# EMS_esp32_wifi_v2_5.net
KiCad netlist of a schematic drawn in EAGLE
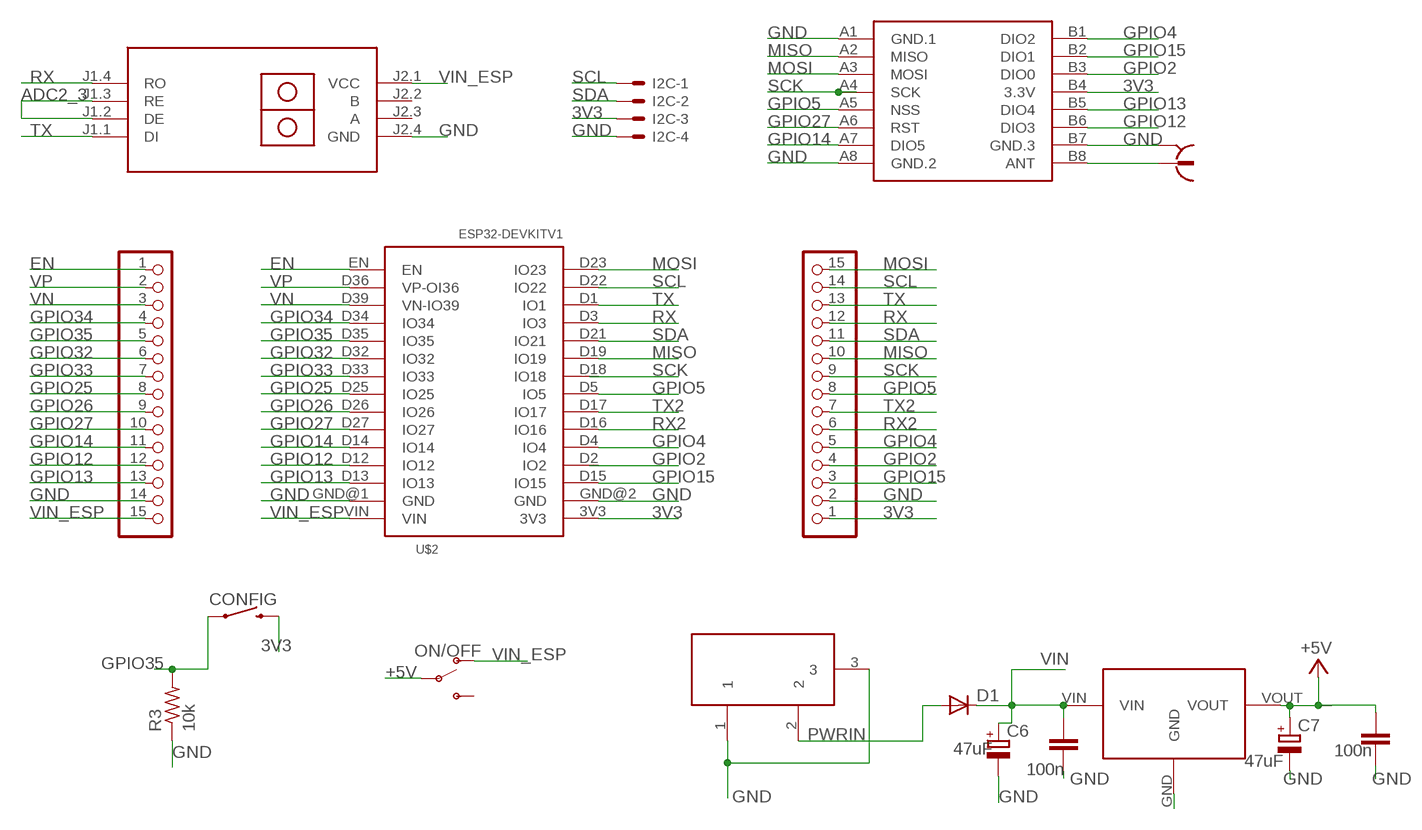
[diagram p0: schematic, sheet 1]

(export (version "E")
  (design (tool "Eeschema 10.0.6"))
  (components
    (comp (ref "C5")
      (value "100n")
      (footprint "eagle-import:C1206")
      (libsource (lib "eagle-import") (part "C-EUC1206"))
    )
    (comp (ref "C6")
      (value "47uF")
      (footprint "eagle-import:PANASONIC_D")
      (libsource (lib "eagle-import") (part "CPOL-EUD"))
    )
    (comp (ref "C7")
      (value "47uF")
      (footprint "eagle-import:PANASONIC_D")
      (libsource (lib "eagle-import") (part "CPOL-EUD"))
    )
    (comp (ref "C14")
      (value "100n")
      (footprint "eagle-import:C1206")
      (libsource (lib "eagle-import") (part "C-EUC1206"))
    )
    (comp (ref "CONFIG")
      (value "MOMENTARY-SWITCH-SPST-PTH-6.0MM")
      (footprint "eagle-import:TACTILE_SWITCH_PTH_6.0MM")
      (libsource (lib "eagle-import") (part "MOMENTARY-SWITCH-SPST-PTH-6.0MM"))
    )
    (comp (ref "D1")
      (value "DIODE-SMB")
      (footprint "eagle-import:SMB")
      (libsource (lib "eagle-import") (part "DIODE-SMB"))
    )
    (comp (ref "I2C")
      (value "22-23-2041")
      (footprint "eagle-import:22-23-2041")
      (fields (field (name "MF") "MOLEX"))
      (libsource (lib "eagle-import") (part "22-23-2041"))
    )
    (comp (ref "JP1")
      (value "PINHD-1X15")
      (footprint "eagle-import:1X15")
      (libsource (lib "eagle-import") (part "PINHD-1X15"))
    )
    (comp (ref "JP2")
      (value "PINHD-1X15")
      (footprint "eagle-import:1X15")
      (libsource (lib "eagle-import") (part "PINHD-1X15"))
    )
    (comp (ref "ON/OFF")
      (value "SWITCH-SPDT-PTH-11.6X4.0MM")
      (footprint "eagle-import:SWITCH_SPDT_PTH_11.6X4.0MM")
      (libsource (lib "eagle-import") (part "SWITCH-SPDT-PTH-11.6X4.0MM"))
    )
    (comp (ref "R3")
      (value "10k")
      (footprint "eagle-import:0204_7")
      (libsource (lib "eagle-import") (part "R-US_0204/7"))
    )
    (comp (ref "U$1")
      (value "RS485-TTL-CONVERTER")
      (footprint "eagle-import:RS485-TTL-CONVERTER")
      (libsource (lib "eagle-import") (part "RS485-TTL-CONVERTER"))
    )
    (comp (ref "U$2")
      (value "ESP32DEVKITV1")
      (footprint "eagle-import:ESP32-DEVKITV1")
      (libsource (lib "eagle-import") (part "ESP32DEVKITV1"))
    )
    (comp (ref "U$3")
      (value "SMARTPRJ_POWERSUPPLY_DC21MMX")
      (footprint "eagle-import:SMARTPRJ_POWERSUPPLY_DC-21MM")
      (libsource (lib "eagle-import") (part "SMARTPRJ_POWERSUPPLY_DC21MMX"))
    )
    (comp (ref "U$4")
      (value "7805-TO263_7805")
      (footprint "eagle-import:7805-TO263_TO263")
      (libsource (lib "eagle-import") (part "7805-TO263_7805"))
    )
    (comp (ref "U$5")
      (value "WIRELESS-LORA-RFM95W#SMD")
      (footprint "eagle-import:WIRELESS-LORA-RFM95W#SMD")
      (libsource (lib "eagle-import") (part "WIRELESS-LORA-RFM95W#SMD"))
    )
    (comp (ref "X1")
      (value "734120110")
      (footprint "eagle-import:734120110")
      (libsource (lib "eagle-import") (part "734120110"))
    )
  )
  (nets
    (net (code "1") (name "+5V") (class "Default")
      (node (ref "C14") (pin "2") (pinfunction "2_2") (pintype "passive"))
      (node (ref "C7") (pin "+") (pinfunction "+_+") (pintype "passive"))
      (node (ref "ON/OFF") (pin "2") (pinfunction "P_2") (pintype "passive"))
      (node (ref "U$4") (pin "VOUT") (pinfunction "VOUT_VOUT") (pintype "bidirectional"))
    )
    (net (code "2") (name "/3V3") (class "Default")
      (node (ref "CONFIG") (pin "3") (pinfunction "2_3") (pintype "passive"))
      (node (ref "I2C") (pin "3") (pinfunction "S_3") (pintype "passive"))
      (node (ref "JP2") (pin "1") (pinfunction "1_1") (pintype "passive"))
      (node (ref "U$2") (pin "3V3") (pinfunction "3V3_3V3") (pintype "bidirectional"))
      (node (ref "U$5") (pin "B4") (pinfunction "3.3V_B4") (pintype "power_in"))
    )
    (net (code "3") (name "/ADC2_3") (class "Default")
      (node (ref "U$1") (pin "J1.2") (pinfunction "DE_J1.2") (pintype "passive"))
      (node (ref "U$1") (pin "J1.3") (pinfunction "RE_J1.3") (pintype "passive"))
    )
    (net (code "4") (name "/EN") (class "Default")
      (node (ref "JP1") (pin "1") (pinfunction "1_1") (pintype "passive"))
      (node (ref "U$2") (pin "EN") (pinfunction "EN_EN") (pintype "bidirectional"))
    )
    (net (code "5") (name "/GND") (class "Default")
      (node (ref "C14") (pin "1") (pinfunction "1_1") (pintype "passive"))
      (node (ref "C5") (pin "1") (pinfunction "1_1") (pintype "passive"))
      (node (ref "C6") (pin "-") (pinfunction "-_-") (pintype "passive"))
      (node (ref "C7") (pin "-") (pinfunction "-_-") (pintype "passive"))
      (node (ref "I2C") (pin "4") (pinfunction "S_4") (pintype "passive"))
      (node (ref "JP1") (pin "14") (pinfunction "14_14") (pintype "passive"))
      (node (ref "JP2") (pin "2") (pinfunction "2_2") (pintype "passive"))
      (node (ref "R3") (pin "1") (pinfunction "1_1") (pintype "passive"))
      (node (ref "U$1") (pin "J2.4") (pinfunction "GND_J2.4") (pintype "power_in"))
      (node (ref "U$2") (pin "GND@1") (pinfunction "GND_GND@1") (pintype "bidirectional"))
      (node (ref "U$2") (pin "GND@2") (pinfunction "GND_GND@2") (pintype "bidirectional"))
      (node (ref "U$3") (pin "1") (pinfunction "1_1") (pintype "power_in"))
      (node (ref "U$3") (pin "3") (pinfunction "3_3") (pintype "power_in"))
      (node (ref "U$4") (pin "GND") (pinfunction "GND_GND") (pintype "bidirectional"))
      (node (ref "U$5") (pin "A1") (pinfunction "GND.1_A1") (pintype "power_in"))
      (node (ref "U$5") (pin "A8") (pinfunction "GND.2_A8") (pintype "power_in"))
      (node (ref "U$5") (pin "B7") (pinfunction "GND.3_B7") (pintype "power_in"))
      (node (ref "X1") (pin "S@1") (pinfunction "2_S@1") (pintype "passive"))
      (node (ref "X1") (pin "S@2") (pinfunction "2_S@2") (pintype "passive"))
      (node (ref "X1") (pin "S@3") (pinfunction "2_S@3") (pintype "passive"))
    )
    (net (code "6") (name "/GPIO2") (class "Default")
      (node (ref "JP2") (pin "4") (pinfunction "4_4") (pintype "passive"))
      (node (ref "U$2") (pin "D2") (pinfunction "IO2_D2") (pintype "bidirectional"))
      (node (ref "U$5") (pin "B3") (pinfunction "DIO0_B3") (pintype "bidirectional"))
    )
    (net (code "7") (name "/GPIO4") (class "Default")
      (node (ref "JP2") (pin "5") (pinfunction "5_5") (pintype "passive"))
      (node (ref "U$2") (pin "D4") (pinfunction "IO4_D4") (pintype "bidirectional"))
      (node (ref "U$5") (pin "B1") (pinfunction "DIO2_B1") (pintype "bidirectional"))
    )
    (net (code "8") (name "/GPIO5") (class "Default")
      (node (ref "JP2") (pin "8") (pinfunction "8_8") (pintype "passive"))
      (node (ref "U$2") (pin "D5") (pinfunction "IO5_D5") (pintype "bidirectional"))
      (node (ref "U$5") (pin "A5") (pinfunction "NSS_A5") (pintype "bidirectional"))
    )
    (net (code "9") (name "/GPIO12") (class "Default")
      (node (ref "JP1") (pin "12") (pinfunction "12_12") (pintype "passive"))
      (node (ref "U$2") (pin "D12") (pinfunction "IO12_D12") (pintype "bidirectional"))
      (node (ref "U$5") (pin "B6") (pinfunction "DIO3_B6") (pintype "bidirectional"))
    )
    (net (code "10") (name "/GPIO13") (class "Default")
      (node (ref "JP1") (pin "13") (pinfunction "13_13") (pintype "passive"))
      (node (ref "U$2") (pin "D13") (pinfunction "IO13_D13") (pintype "bidirectional"))
      (node (ref "U$5") (pin "B5") (pinfunction "DIO4_B5") (pintype "bidirectional"))
    )
    (net (code "11") (name "/GPIO14") (class "Default")
      (node (ref "JP1") (pin "11") (pinfunction "11_11") (pintype "passive"))
      (node (ref "U$2") (pin "D14") (pinfunction "IO14_D14") (pintype "bidirectional"))
      (node (ref "U$5") (pin "A7") (pinfunction "DIO5_A7") (pintype "bidirectional"))
    )
    (net (code "12") (name "/GPIO15") (class "Default")
      (node (ref "JP2") (pin "3") (pinfunction "3_3") (pintype "passive"))
      (node (ref "U$2") (pin "D15") (pinfunction "IO15_D15") (pintype "bidirectional"))
      (node (ref "U$5") (pin "B2") (pinfunction "DIO1_B2") (pintype "bidirectional"))
    )
    (net (code "13") (name "/GPIO25") (class "Default")
      (node (ref "JP1") (pin "8") (pinfunction "8_8") (pintype "passive"))
      (node (ref "U$2") (pin "D25") (pinfunction "IO25_D25") (pintype "bidirectional"))
    )
    (net (code "14") (name "/GPIO26") (class "Default")
      (node (ref "JP1") (pin "9") (pinfunction "9_9") (pintype "passive"))
      (node (ref "U$2") (pin "D26") (pinfunction "IO26_D26") (pintype "bidirectional"))
    )
    (net (code "15") (name "/GPIO27") (class "Default")
      (node (ref "JP1") (pin "10") (pinfunction "10_10") (pintype "passive"))
      (node (ref "U$2") (pin "D27") (pinfunction "IO27_D27") (pintype "bidirectional"))
      (node (ref "U$5") (pin "A6") (pinfunction "RST_A6") (pintype "bidirectional"))
    )
    (net (code "16") (name "/GPIO32") (class "Default")
      (node (ref "JP1") (pin "6") (pinfunction "6_6") (pintype "passive"))
      (node (ref "U$2") (pin "D32") (pinfunction "IO32_D32") (pintype "bidirectional"))
    )
    (net (code "17") (name "/GPIO33") (class "Default")
      (node (ref "JP1") (pin "7") (pinfunction "7_7") (pintype "passive"))
      (node (ref "U$2") (pin "D33") (pinfunction "IO33_D33") (pintype "bidirectional"))
    )
    (net (code "18") (name "/GPIO34") (class "Default")
      (node (ref "JP1") (pin "4") (pinfunction "4_4") (pintype "passive"))
      (node (ref "U$2") (pin "D34") (pinfunction "IO34_D34") (pintype "bidirectional"))
    )
    (net (code "19") (name "/GPIO35") (class "Default")
      (node (ref "CONFIG") (pin "1") (pinfunction "1_1") (pintype "passive"))
      (node (ref "JP1") (pin "5") (pinfunction "5_5") (pintype "passive"))
      (node (ref "R3") (pin "2") (pinfunction "2_2") (pintype "passive"))
      (node (ref "U$2") (pin "D35") (pinfunction "IO35_D35") (pintype "bidirectional"))
    )
    (net (code "20") (name "/MISO") (class "Default")
      (node (ref "JP2") (pin "10") (pinfunction "10_10") (pintype "passive"))
      (node (ref "U$2") (pin "D19") (pinfunction "IO19_D19") (pintype "bidirectional"))
      (node (ref "U$5") (pin "A2") (pinfunction "MISO_A2") (pintype "bidirectional"))
    )
    (net (code "21") (name "/MOSI") (class "Default")
      (node (ref "JP2") (pin "15") (pinfunction "15_15") (pintype "passive"))
      (node (ref "U$2") (pin "D23") (pinfunction "IO23_D23") (pintype "bidirectional"))
      (node (ref "U$5") (pin "A3") (pinfunction "MOSI_A3") (pintype "bidirectional"))
    )
    (net (code "22") (name "/PWRIN") (class "Default")
      (node (ref "D1") (pin "A") (pinfunction "A_A") (pintype "passive"))
      (node (ref "U$3") (pin "2") (pinfunction "2_2") (pintype "power_in"))
    )
    (net (code "23") (name "/RX") (class "Default")
      (node (ref "JP2") (pin "12") (pinfunction "12_12") (pintype "passive"))
      (node (ref "U$1") (pin "J1.4") (pinfunction "RO_J1.4") (pintype "passive"))
      (node (ref "U$2") (pin "D3") (pinfunction "IO3_D3") (pintype "bidirectional"))
    )
    (net (code "24") (name "/RX2") (class "Default")
      (node (ref "JP2") (pin "6") (pinfunction "6_6") (pintype "passive"))
      (node (ref "U$2") (pin "D16") (pinfunction "IO16_D16") (pintype "bidirectional"))
    )
    (net (code "25") (name "/SCK") (class "Default")
      (node (ref "JP2") (pin "9") (pinfunction "9_9") (pintype "passive"))
      (node (ref "U$2") (pin "D18") (pinfunction "IO18_D18") (pintype "bidirectional"))
      (node (ref "U$5") (pin "A4") (pinfunction "SCK_A4") (pintype "bidirectional"))
    )
    (net (code "26") (name "/SCL") (class "Default")
      (node (ref "I2C") (pin "1") (pinfunction "S_1") (pintype "passive"))
      (node (ref "JP2") (pin "14") (pinfunction "14_14") (pintype "passive"))
      (node (ref "U$2") (pin "D22") (pinfunction "IO22_D22") (pintype "bidirectional"))
    )
    (net (code "27") (name "/SDA") (class "Default")
      (node (ref "I2C") (pin "2") (pinfunction "S_2") (pintype "passive"))
      (node (ref "JP2") (pin "11") (pinfunction "11_11") (pintype "passive"))
      (node (ref "U$2") (pin "D21") (pinfunction "IO21_D21") (pintype "bidirectional"))
    )
    (net (code "28") (name "/TX") (class "Default")
      (node (ref "JP2") (pin "13") (pinfunction "13_13") (pintype "passive"))
      (node (ref "U$1") (pin "J1.1") (pinfunction "DI_J1.1") (pintype "passive"))
      (node (ref "U$2") (pin "D1") (pinfunction "IO1_D1") (pintype "bidirectional"))
    )
    (net (code "29") (name "/TX2") (class "Default")
      (node (ref "JP2") (pin "7") (pinfunction "7_7") (pintype "passive"))
      (node (ref "U$2") (pin "D17") (pinfunction "IO17_D17") (pintype "bidirectional"))
    )
    (net (code "30") (name "/VIN") (class "Default")
      (node (ref "C5") (pin "2") (pinfunction "2_2") (pintype "passive"))
      (node (ref "C6") (pin "+") (pinfunction "+_+") (pintype "passive"))
      (node (ref "D1") (pin "C") (pinfunction "C_C") (pintype "passive"))
      (node (ref "U$4") (pin "VIN") (pinfunction "VIN_VIN") (pintype "bidirectional"))
    )
    (net (code "31") (name "/VIN_ESP") (class "Default")
      (node (ref "JP1") (pin "15") (pinfunction "15_15") (pintype "passive"))
      (node (ref "ON/OFF") (pin "1") (pinfunction "O_1") (pintype "passive"))
      (node (ref "U$1") (pin "J2.1") (pinfunction "VCC_J2.1") (pintype "power_in"))
      (node (ref "U$2") (pin "VIN") (pinfunction "VIN_VIN") (pintype "bidirectional"))
    )
    (net (code "32") (name "/VN") (class "Default")
      (node (ref "JP1") (pin "3") (pinfunction "3_3") (pintype "passive"))
      (node (ref "U$2") (pin "D39") (pinfunction "VN-IO39_D39") (pintype "bidirectional"))
    )
    (net (code "33") (name "/VP") (class "Default")
      (node (ref "JP1") (pin "2") (pinfunction "2_2") (pintype "passive"))
      (node (ref "U$2") (pin "D36") (pinfunction "VP-OI36_D36") (pintype "bidirectional"))
    )
    (net (code "34") (name "Net-(U$5-ANT)") (class "Default")
      (node (ref "U$5") (pin "B8") (pinfunction "ANT_B8") (pintype "passive"))
      (node (ref "X1") (pin "1") (pinfunction "1_1") (pintype "passive"))
    )
    (net (code "35") (name "unconnected-(ON/OFF-S-Pad3)") (class "Default")
      (node (ref "ON/OFF") (pin "3") (pinfunction "S_3") (pintype "passive"))
    )
    (net (code "36") (name "unconnected-(U$1-A-PadJ2.3)") (class "Default")
      (node (ref "U$1") (pin "J2.3") (pinfunction "A_J2.3") (pintype "passive"))
    )
    (net (code "37") (name "unconnected-(U$1-B-PadJ2.2)") (class "Default")
      (node (ref "U$1") (pin "J2.2") (pinfunction "B_J2.2") (pintype "passive"))
    )
  )
)
